# PWM_CON_Sensors.net
KiCad netlist of a schematic drawn in Altium Designer
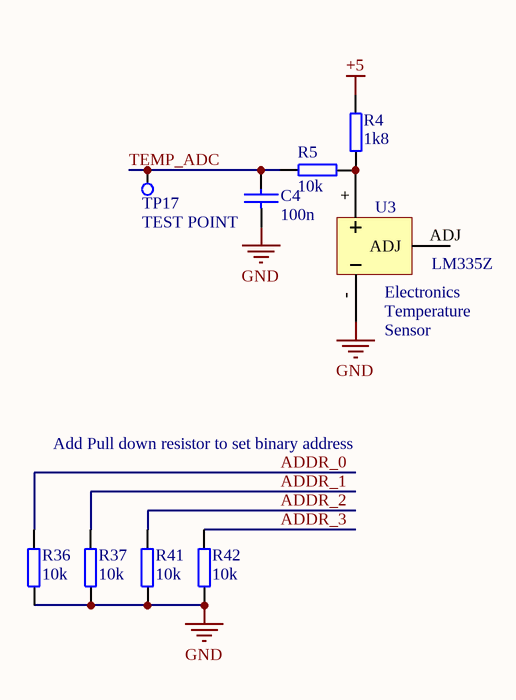
[diagram p0: PWM_CON_Sensors.SchDoc]

(export (version "E")
  (design (tool "Eeschema 10.0.6"))
  (components
    (comp (ref "C4")
      (value "100n")
      (footprint "0603")
      (fields (field (name "PARTNO") "R8835"))
      (libsource (lib "*") (part "CAP"))
    )
    (comp (ref "R4")
      (value "1k8")
      (footprint "0603")
      (description "1% Resistor")
      (fields (field (name "PARTNO") "R1614"))
      (libsource (lib "DEVICE") (part "RES8"))
    )
    (comp (ref "R5")
      (value "10k")
      (footprint "0603")
      (description "1% Resistor")
      (fields (field (name "PARTNO") "R1668"))
      (libsource (lib "DEVICE") (part "RES8"))
    )
    (comp (ref "R36")
      (value "10k")
      (footprint "0603")
      (description "1% Resistor")
      (fields (field (name "PARTNO") "R1668"))
      (libsource (lib "DEVICE") (part "RES8"))
    )
    (comp (ref "R37")
      (value "10k")
      (footprint "0603")
      (description "1% Resistor")
      (fields (field (name "PARTNO") "R1668"))
      (libsource (lib "DEVICE") (part "RES8"))
    )
    (comp (ref "R41")
      (value "10k")
      (footprint "0603")
      (description "1% Resistor")
      (fields (field (name "PARTNO") "R1668"))
      (libsource (lib "DEVICE") (part "RES8"))
    )
    (comp (ref "R42")
      (value "10k")
      (footprint "0603")
      (description "1% Resistor")
      (fields (field (name "PARTNO") "R1668"))
      (libsource (lib "DEVICE") (part "RES8"))
    )
    (comp (ref "TP17")
      (value "TEST POINT")
      (footprint "TEST POINT")
      (description "Probe compatible test point")
      (libsource (lib "DEVICE") (part "TEST POINT"))
    )
    (comp (ref "U3")
      (value "LM335Z")
      (footprint "TO-92_LM335")
      (fields (field (name "PARTNO") "Z2530"))
      (libsource (lib "D_LINEAR") (part "LM335Z"))
    )
  )
  (nets
    (net (code "1") (name "+5") (class "Default") (node (ref "R4") (pin "1") (pintype "passive")))
    (net (code "2") (name "/ADDR_0") (class "Default") (node (ref "R36") (pin "2") (pintype "passive")))
    (net (code "3") (name "/ADDR_1") (class "Default") (node (ref "R37") (pin "2") (pintype "passive")))
    (net (code "4") (name "/ADDR_2") (class "Default") (node (ref "R41") (pin "2") (pintype "passive")))
    (net (code "5") (name "/ADDR_3") (class "Default") (node (ref "R42") (pin "2") (pintype "passive")))
    (net (code "6") (name "/TEMP_ADC") (class "Default")
      (node (ref "C4") (pin "2") (pintype "passive"))
      (node (ref "R5") (pin "2") (pintype "passive"))
      (node (ref "TP17") (pin "1") (pinfunction "1_1") (pintype "passive"))
    )
    (net (code "7") (name "GND") (class "Default")
      (node (ref "C4") (pin "1") (pintype "passive"))
      (node (ref "R36") (pin "1") (pintype "passive"))
      (node (ref "R37") (pin "1") (pintype "passive"))
      (node (ref "R41") (pin "1") (pintype "passive"))
      (node (ref "R42") (pin "1") (pintype "passive"))
      (node (ref "U3") (pin "-") (pinfunction "-_-") (pintype "passive"))
    )
    (net (code "8") (name "Net-(R4-Pad2)") (class "Default")
      (node (ref "R4") (pin "2") (pintype "passive"))
      (node (ref "R5") (pin "1") (pintype "passive"))
      (node (ref "U3") (pin "+") (pinfunction "+_+") (pintype "passive"))
    )
    (net (code "9") (name "unconnected-(U3-PadADJ)") (class "Default")
      (node (ref "U3") (pin "ADJ") (pinfunction "ADJ_ADJ") (pintype "passive"))
    )
  )
)
